# DSO_CPLD.net
KiCad netlist of a schematic drawn in Altium Designer
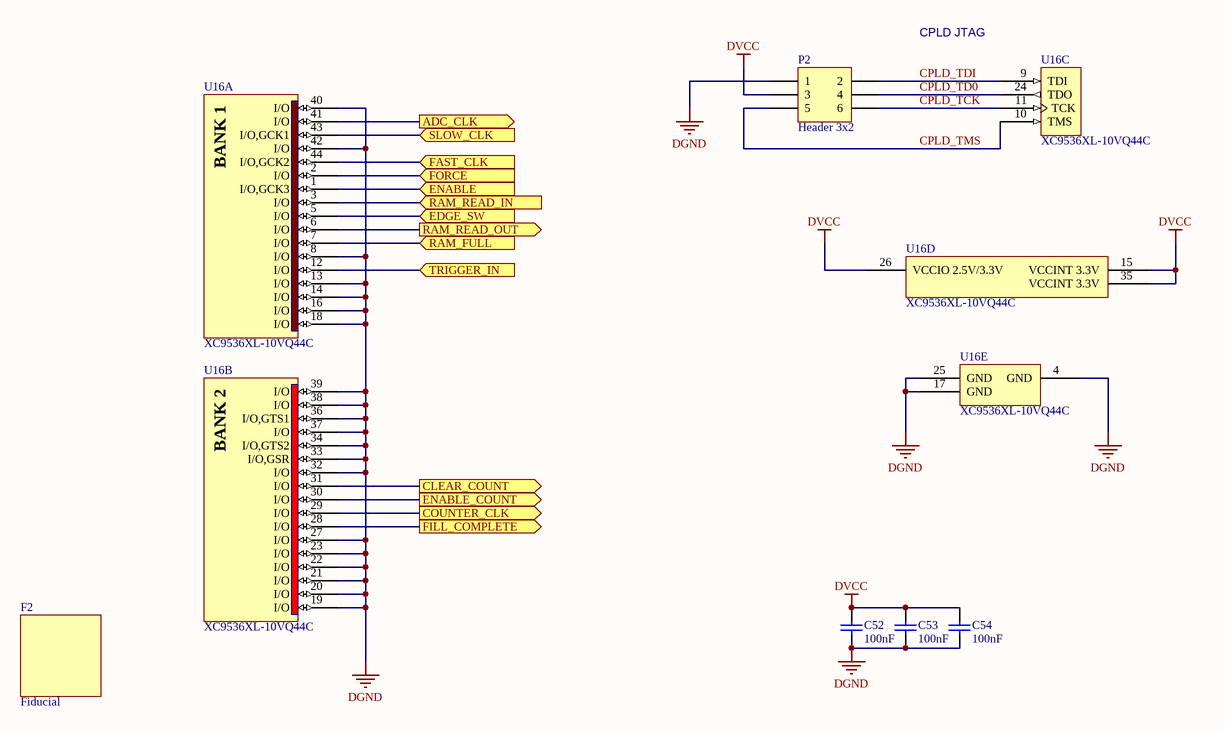
[diagram p0: DSO_CPLD.SchDoc]

(export (version "E")
  (design (tool "Eeschema 10.0.6"))
  (components
    (comp (ref "C52")
      (value "100nF")
      (footprint "0805C")
      (description "Capacitor")
      (fields (field (name "REVIEWED BY") "RM - 2018/08/05"))
      (libsource (lib "DSO") (part "C"))
    )
    (comp (ref "C53")
      (value "100nF")
      (footprint "0805C")
      (description "Capacitor")
      (fields (field (name "REVIEWED BY") "RM - 2018/08/05"))
      (libsource (lib "DSO") (part "C"))
    )
    (comp (ref "C54")
      (value "100nF")
      (footprint "0805C")
      (description "Capacitor")
      (fields (field (name "REVIEWED BY") "RM - 2018/08/05"))
      (libsource (lib "DSO") (part "C"))
    )
    (comp (ref "F2") (value "Fiducial") (footprint "Fiducial") (libsource (lib "DSO") (part "Fiducial")))
    (comp (ref "P2")
      (value "Header 3x2")
      (footprint "HDR3x2")
      (description "Header, 5-Pin")
      (fields (field (name "REVIEWED BY") "RM - 2018/08/05"))
      (libsource (lib "DSO") (part "Header 3x2"))
    )
    (comp (ref "U16")
      (value "XC9536XL-10VQ44C")
      (footprint "VQ44_L")
      (fields (field (name "REVIEWED BY") "RM - 2018/08/05"))
      (libsource (lib "DSO") (part "XC9536XL-10VQG44C"))
    )
  )
  (nets
    (net (code "1") (name "/ADC_CLK") (class "Default")
      (node (ref "U16") (pin "41") (pinfunction "I/O_41") (pintype "bidirectional"))
    )
    (net (code "2") (name "/CLEAR_COUNT") (class "Default")
      (node (ref "U16") (pin "31") (pinfunction "I/O_31") (pintype "bidirectional"))
    )
    (net (code "3") (name "/COUNTER_CLK") (class "Default")
      (node (ref "U16") (pin "29") (pinfunction "I/O_29") (pintype "bidirectional"))
    )
    (net (code "4") (name "/CPLD_TCK") (class "Default")
      (node (ref "P2") (pin "6") (pinfunction "6_6") (pintype "passive"))
      (node (ref "U16") (pin "11") (pinfunction "TCK_11") (pintype "input"))
    )
    (net (code "5") (name "/CPLD_TD0") (class "Default")
      (node (ref "P2") (pin "4") (pinfunction "4_4") (pintype "passive"))
      (node (ref "U16") (pin "24") (pinfunction "TDO_24") (pintype "output"))
    )
    (net (code "6") (name "/CPLD_TDI") (class "Default")
      (node (ref "P2") (pin "2") (pinfunction "2_2") (pintype "passive"))
      (node (ref "U16") (pin "9") (pinfunction "TDI_9") (pintype "input"))
    )
    (net (code "7") (name "/CPLD_TMS") (class "Default")
      (node (ref "P2") (pin "5") (pinfunction "5_5") (pintype "passive"))
      (node (ref "U16") (pin "10") (pinfunction "TMS_10") (pintype "input"))
    )
    (net (code "8") (name "/EDGE_SW") (class "Default")
      (node (ref "U16") (pin "5") (pinfunction "I/O_5") (pintype "bidirectional"))
    )
    (net (code "9") (name "/ENABLE") (class "Default")
      (node (ref "U16") (pin "1") (pinfunction "I/O,GCK3_1") (pintype "bidirectional"))
    )
    (net (code "10") (name "/ENABLE_COUNT") (class "Default")
      (node (ref "U16") (pin "30") (pinfunction "I/O_30") (pintype "bidirectional"))
    )
    (net (code "11") (name "/FAST_CLK") (class "Default")
      (node (ref "U16") (pin "44") (pinfunction "I/O,GCK2_44") (pintype "bidirectional"))
    )
    (net (code "12") (name "/FILL_COMPLETE") (class "Default")
      (node (ref "U16") (pin "28") (pinfunction "I/O_28") (pintype "bidirectional"))
    )
    (net (code "13") (name "/FORCE") (class "Default")
      (node (ref "U16") (pin "2") (pinfunction "I/O_2") (pintype "bidirectional"))
    )
    (net (code "14") (name "/RAM_FULL") (class "Default")
      (node (ref "U16") (pin "7") (pinfunction "I/O_7") (pintype "bidirectional"))
    )
    (net (code "15") (name "/RAM_READ_IN") (class "Default")
      (node (ref "U16") (pin "3") (pinfunction "I/O_3") (pintype "bidirectional"))
    )
    (net (code "16") (name "/RAM_READ_OUT") (class "Default")
      (node (ref "U16") (pin "6") (pinfunction "I/O_6") (pintype "bidirectional"))
    )
    (net (code "17") (name "/SLOW_CLK") (class "Default")
      (node (ref "U16") (pin "43") (pinfunction "I/O,GCK1_43") (pintype "bidirectional"))
    )
    (net (code "18") (name "/TRIGGER_IN") (class "Default")
      (node (ref "U16") (pin "12") (pinfunction "I/O_12") (pintype "bidirectional"))
    )
    (net (code "19") (name "DGND") (class "Default")
      (node (ref "C52") (pin "2") (pinfunction "2_2") (pintype "passive"))
      (node (ref "C53") (pin "2") (pinfunction "2_2") (pintype "passive"))
      (node (ref "C54") (pin "2") (pinfunction "2_2") (pintype "passive"))
      (node (ref "P2") (pin "1") (pinfunction "1_1") (pintype "passive"))
      (node (ref "U16") (pin "13") (pinfunction "I/O_13") (pintype "bidirectional"))
      (node (ref "U16") (pin "14") (pinfunction "I/O_14") (pintype "bidirectional"))
      (node (ref "U16") (pin "16") (pinfunction "I/O_16") (pintype "bidirectional"))
      (node (ref "U16") (pin "17") (pinfunction "GND_17") (pintype "power_in"))
      (node (ref "U16") (pin "18") (pinfunction "I/O_18") (pintype "bidirectional"))
      (node (ref "U16") (pin "19") (pinfunction "I/O_19") (pintype "bidirectional"))
      (node (ref "U16") (pin "20") (pinfunction "I/O_20") (pintype "bidirectional"))
      (node (ref "U16") (pin "21") (pinfunction "I/O_21") (pintype "bidirectional"))
      (node (ref "U16") (pin "22") (pinfunction "I/O_22") (pintype "bidirectional"))
      (node (ref "U16") (pin "23") (pinfunction "I/O_23") (pintype "bidirectional"))
      (node (ref "U16") (pin "25") (pinfunction "GND_25") (pintype "power_in"))
      (node (ref "U16") (pin "27") (pinfunction "I/O_27") (pintype "bidirectional"))
      (node (ref "U16") (pin "32") (pinfunction "I/O_32") (pintype "bidirectional"))
      (node (ref "U16") (pin "33") (pinfunction "I/O,GSR_33") (pintype "bidirectional"))
      (node (ref "U16") (pin "34") (pinfunction "I/O,GTS2_34") (pintype "bidirectional"))
      (node (ref "U16") (pin "36") (pinfunction "I/O,GTS1_36") (pintype "bidirectional"))
      (node (ref "U16") (pin "37") (pinfunction "I/O_37") (pintype "bidirectional"))
      (node (ref "U16") (pin "38") (pinfunction "I/O_38") (pintype "bidirectional"))
      (node (ref "U16") (pin "39") (pinfunction "I/O_39") (pintype "bidirectional"))
      (node (ref "U16") (pin "4") (pinfunction "GND_4") (pintype "power_in"))
      (node (ref "U16") (pin "40") (pinfunction "I/O_40") (pintype "bidirectional"))
      (node (ref "U16") (pin "42") (pinfunction "I/O_42") (pintype "bidirectional"))
      (node (ref "U16") (pin "8") (pinfunction "I/O_8") (pintype "bidirectional"))
    )
    (net (code "20") (name "DVCC") (class "Default")
      (node (ref "C52") (pin "1") (pinfunction "1_1") (pintype "passive"))
      (node (ref "C53") (pin "1") (pinfunction "1_1") (pintype "passive"))
      (node (ref "C54") (pin "1") (pinfunction "1_1") (pintype "passive"))
      (node (ref "P2") (pin "3") (pinfunction "3_3") (pintype "passive"))
      (node (ref "U16") (pin "15") (pinfunction "VCCINT_3.3V_15") (pintype "power_in"))
      (node (ref "U16") (pin "26") (pinfunction "VCCIO_2.5V/3.3V_26") (pintype "power_in"))
      (node (ref "U16") (pin "35") (pinfunction "VCCINT_3.3V_35") (pintype "power_in"))
    )
  )
)
